# swd.net
KiCad netlist of a schematic drawn in EAGLE
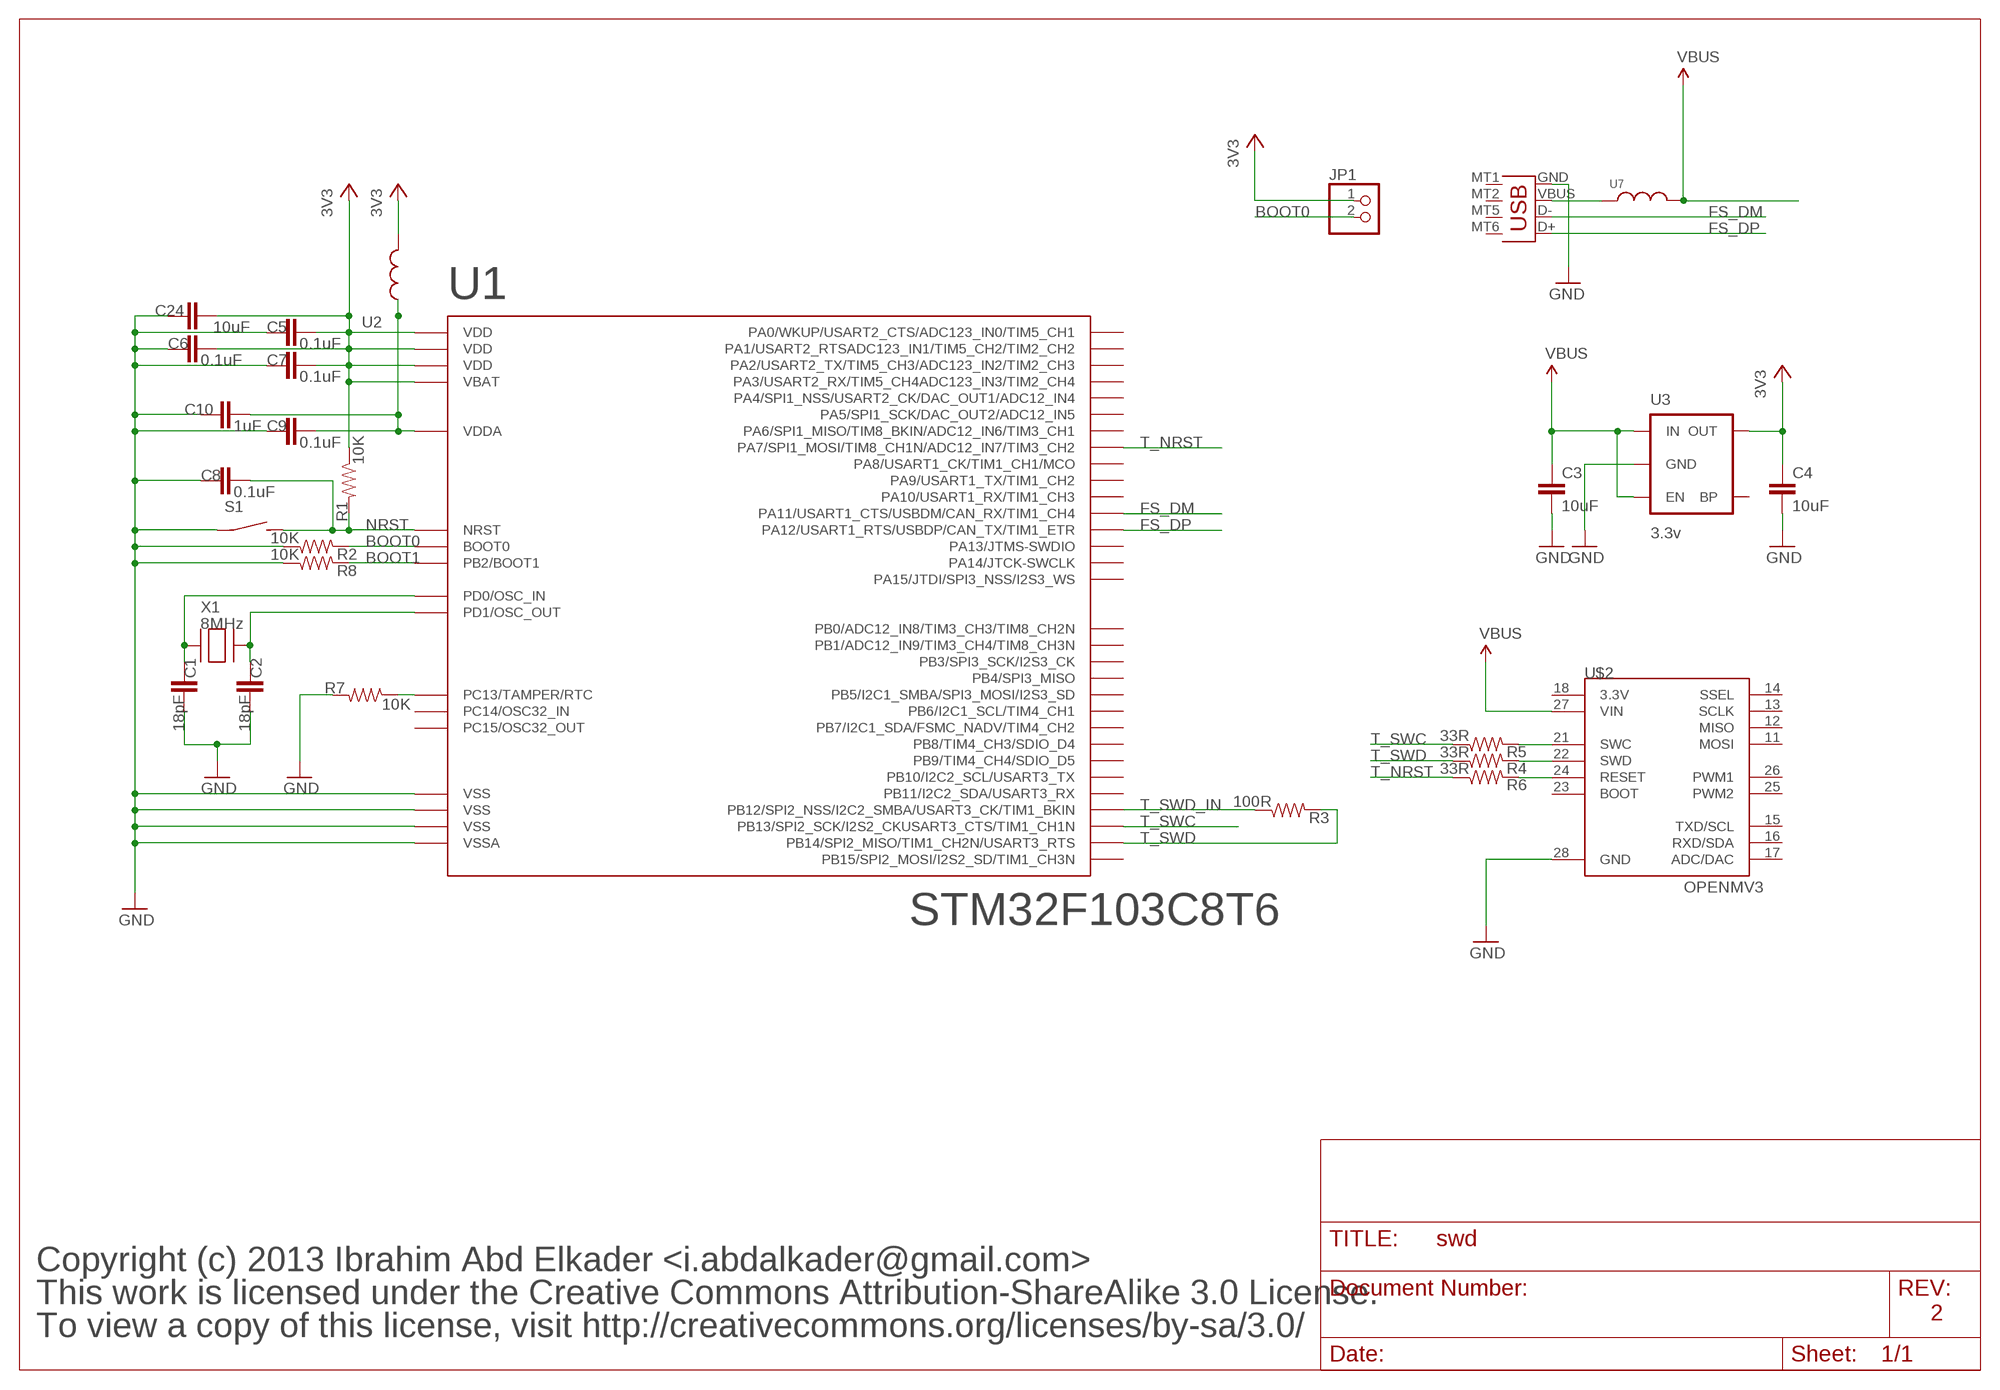
[diagram p0: schematic, sheet 1]

(export (version "E")
  (design (tool "Eeschema 10.0.6"))
  (components
    (comp (ref "C1")
      (value "18pF")
      (footprint "eagle-import:0603-CAP")
      (libsource (lib "eagle-import") (part "CAP0603-CAP"))
    )
    (comp (ref "C2")
      (value "18pF")
      (footprint "eagle-import:0603-CAP")
      (libsource (lib "eagle-import") (part "CAP0603-CAP"))
    )
    (comp (ref "C3")
      (value "10uF")
      (footprint "eagle-import:0805")
      (libsource (lib "eagle-import") (part "CAP0805"))
    )
    (comp (ref "C4")
      (value "10uF")
      (footprint "eagle-import:0805")
      (libsource (lib "eagle-import") (part "CAP0805"))
    )
    (comp (ref "C5")
      (value "0.1uF")
      (footprint "eagle-import:0603-CAP")
      (libsource (lib "eagle-import") (part "CAP0603-CAP"))
    )
    (comp (ref "C6")
      (value "0.1uF")
      (footprint "eagle-import:0603-CAP")
      (libsource (lib "eagle-import") (part "CAP0603-CAP"))
    )
    (comp (ref "C7")
      (value "0.1uF")
      (footprint "eagle-import:0603-CAP")
      (libsource (lib "eagle-import") (part "CAP0603-CAP"))
    )
    (comp (ref "C8")
      (value "0.1uF")
      (footprint "eagle-import:0603-CAP")
      (libsource (lib "eagle-import") (part "CAP0603-CAP"))
    )
    (comp (ref "C9")
      (value "0.1uF")
      (footprint "eagle-import:0603-CAP")
      (libsource (lib "eagle-import") (part "CAP0603-CAP"))
    )
    (comp (ref "C10")
      (value "1uF")
      (footprint "eagle-import:0603-CAP")
      (libsource (lib "eagle-import") (part "CAP0603-CAP"))
    )
    (comp (ref "C24")
      (value "10uF")
      (footprint "eagle-import:0805")
      (libsource (lib "eagle-import") (part "CAP0805"))
    )
    (comp (ref "JP1")
      (value "PINHD-1X2")
      (footprint "eagle-import:1X02")
      (libsource (lib "eagle-import") (part "PINHD-1X2"))
    )
    (comp (ref "R1")
      (value "10K")
      (footprint "eagle-import:0603-RES")
      (libsource (lib "eagle-import") (part "RESISTOR0603-RES"))
    )
    (comp (ref "R2")
      (value "10K")
      (footprint "eagle-import:0603-RES")
      (libsource (lib "eagle-import") (part "RESISTOR0603-RES"))
    )
    (comp (ref "R3")
      (value "100R")
      (footprint "eagle-import:0603-RES")
      (libsource (lib "eagle-import") (part "RESISTOR0603-RES"))
    )
    (comp (ref "R4")
      (value "33R")
      (footprint "eagle-import:0603-RES")
      (libsource (lib "eagle-import") (part "RESISTOR0603-RES"))
    )
    (comp (ref "R5")
      (value "33R")
      (footprint "eagle-import:0603-RES")
      (libsource (lib "eagle-import") (part "RESISTOR0603-RES"))
    )
    (comp (ref "R6")
      (value "33R")
      (footprint "eagle-import:0603-RES")
      (libsource (lib "eagle-import") (part "RESISTOR0603-RES"))
    )
    (comp (ref "R7")
      (value "10K")
      (footprint "eagle-import:0603-RES")
      (libsource (lib "eagle-import") (part "RESISTOR0603-RES"))
    )
    (comp (ref "R8")
      (value "10K")
      (footprint "eagle-import:0603-RES")
      (libsource (lib "eagle-import") (part "RESISTOR0603-RES"))
    )
    (comp (ref "S1")
      (value "SPST_3X4X2")
      (footprint "eagle-import:3X4X2TACT")
      (libsource (lib "eagle-import") (part "SPST_3X4X2"))
    )
    (comp (ref "U$2")
      (value "OPENMV3")
      (footprint "eagle-import:OPENMV3")
      (libsource (lib "eagle-import") (part "OPENMV3"))
    )
    (comp (ref "U1")
      (value "STM32F103C8T6")
      (footprint "eagle-import:LQFP48")
      (libsource (lib "eagle-import") (part "STM32F103C8T6"))
    )
    (comp (ref "U2")
      (value "INDUCTOR0603")
      (footprint "eagle-import:0603")
      (libsource (lib "eagle-import") (part "INDUCTOR0603"))
    )
    (comp (ref "U3")
      (value "3.3v")
      (footprint "eagle-import:SOT23-5")
      (libsource (lib "eagle-import") (part "V_REG_LDOSMD"))
    )
    (comp (ref "U7")
      (value "INDUCTOR0603")
      (footprint "eagle-import:0603")
      (libsource (lib "eagle-import") (part "INDUCTOR0603"))
    )
    (comp (ref "X1")
      (value "8MHz")
      (footprint "eagle-import:NX5032")
      (libsource (lib "eagle-import") (part "XTALNX5032"))
    )
    (comp (ref "X2")
      (value "USB-MICROB")
      (footprint "eagle-import:USB-MICROB")
      (libsource (lib "eagle-import") (part "USB-MICROB"))
    )
  )
  (nets
    (net (code "1") (name "/3.3V") (class "Default")
      (node (ref "U$2") (pin "18") (pinfunction "3.3V_18") (pintype "power_in"))
    )
    (net (code "2") (name "/BOOT0") (class "Default")
      (node (ref "JP1") (pin "2") (pinfunction "2_2") (pintype "passive"))
      (node (ref "R2") (pin "2") (pinfunction "2_2") (pintype "passive"))
      (node (ref "U1") (pin "44") (pinfunction "BOOT0_44") (pintype "bidirectional"))
    )
    (net (code "3") (name "/BOOT1") (class "Default")
      (node (ref "R8") (pin "2") (pinfunction "2_2") (pintype "passive"))
      (node (ref "U1") (pin "20") (pinfunction "PB2/BOOT1_20") (pintype "bidirectional"))
    )
    (net (code "4") (name "/FS_DM") (class "Default")
      (node (ref "U1") (pin "32") (pinfunction "PA11/USART1_CTS/USBDM/CAN_RX/TIM1_CH4_32") (pintype "bidirectional"))
      (node (ref "X2") (pin "D-") (pinfunction "D-_D-") (pintype "bidirectional"))
    )
    (net (code "5") (name "/FS_DP") (class "Default")
      (node (ref "U1") (pin "33") (pinfunction "PA12/USART1_RTS/USBDP/CAN_TX/TIM1_ETR_33") (pintype "bidirectional"))
      (node (ref "X2") (pin "D+") (pinfunction "D+_D+") (pintype "bidirectional"))
    )
    (net (code "6") (name "/NRST") (class "Default")
      (node (ref "C8") (pin "2") (pinfunction "2_2") (pintype "passive"))
      (node (ref "R1") (pin "2") (pinfunction "2_2") (pintype "passive"))
      (node (ref "S1") (pin "P$2") (pinfunction "S_P$2") (pintype "passive"))
      (node (ref "U1") (pin "7") (pinfunction "NRST_7") (pintype "bidirectional"))
    )
    (net (code "7") (name "/T_NRST") (class "Default")
      (node (ref "R6") (pin "1") (pinfunction "1_1") (pintype "passive"))
      (node (ref "U1") (pin "17") (pinfunction "PA7/SPI1_MOSI/TIM8_CH1N/ADC12_IN7/TIM3_CH2_17") (pintype "bidirectional"))
    )
    (net (code "8") (name "/T_SWC") (class "Default")
      (node (ref "R5") (pin "1") (pinfunction "1_1") (pintype "passive"))
      (node (ref "U1") (pin "26") (pinfunction "PB13/SPI2_SCK/I2S2_CKUSART3_CTS/TIM1_CH1N_26") (pintype "bidirectional"))
    )
    (net (code "9") (name "/T_SWD") (class "Default")
      (node (ref "R3") (pin "2") (pinfunction "2_2") (pintype "passive"))
      (node (ref "R4") (pin "1") (pinfunction "1_1") (pintype "passive"))
      (node (ref "U1") (pin "27") (pinfunction "PB14/SPI2_MISO/TIM1_CH2N/USART3_RTS_27") (pintype "bidirectional"))
    )
    (net (code "10") (name "/T_SWD_IN") (class "Default")
      (node (ref "R3") (pin "1") (pinfunction "1_1") (pintype "passive"))
      (node (ref "U1") (pin "25") (pinfunction "PB12/SPI2_NSS/I2C2_SMBA/USART3_CK/TIM1_BKIN_25") (pintype "bidirectional"))
    )
    (net (code "11") (name "3V3") (class "Default")
      (node (ref "C24") (pin "2") (pinfunction "2_2") (pintype "passive"))
      (node (ref "C4") (pin "1") (pinfunction "1_1") (pintype "passive"))
      (node (ref "C5") (pin "2") (pinfunction "2_2") (pintype "passive"))
      (node (ref "C6") (pin "2") (pinfunction "2_2") (pintype "passive"))
      (node (ref "C7") (pin "2") (pinfunction "2_2") (pintype "passive"))
      (node (ref "JP1") (pin "1") (pinfunction "1_1") (pintype "passive"))
      (node (ref "R1") (pin "1") (pinfunction "1_1") (pintype "passive"))
      (node (ref "U1") (pin "1") (pinfunction "VBAT_1") (pintype "power_in"))
      (node (ref "U1") (pin "24") (pinfunction "VDD_24") (pintype "power_in"))
      (node (ref "U1") (pin "36") (pinfunction "VDD_36") (pintype "power_in"))
      (node (ref "U1") (pin "48") (pinfunction "VDD_48") (pintype "power_in"))
      (node (ref "U2") (pin "2") (pinfunction "2_2") (pintype "passive"))
      (node (ref "U3") (pin "5") (pinfunction "OUT_5") (pintype "passive"))
    )
    (net (code "12") (name "GND") (class "Default")
      (node (ref "C1") (pin "1") (pinfunction "1_1") (pintype "passive"))
      (node (ref "C10") (pin "1") (pinfunction "1_1") (pintype "passive"))
      (node (ref "C2") (pin "1") (pinfunction "1_1") (pintype "passive"))
      (node (ref "C24") (pin "1") (pinfunction "1_1") (pintype "passive"))
      (node (ref "C3") (pin "2") (pinfunction "2_2") (pintype "passive"))
      (node (ref "C4") (pin "2") (pinfunction "2_2") (pintype "passive"))
      (node (ref "C5") (pin "1") (pinfunction "1_1") (pintype "passive"))
      (node (ref "C6") (pin "1") (pinfunction "1_1") (pintype "passive"))
      (node (ref "C7") (pin "1") (pinfunction "1_1") (pintype "passive"))
      (node (ref "C8") (pin "1") (pinfunction "1_1") (pintype "passive"))
      (node (ref "C9") (pin "1") (pinfunction "1_1") (pintype "passive"))
      (node (ref "R2") (pin "1") (pinfunction "1_1") (pintype "passive"))
      (node (ref "R7") (pin "2") (pinfunction "2_2") (pintype "passive"))
      (node (ref "R8") (pin "1") (pinfunction "1_1") (pintype "passive"))
      (node (ref "S1") (pin "P$1") (pinfunction "P_P$1") (pintype "passive"))
      (node (ref "U$2") (pin "28") (pinfunction "GND_28") (pintype "power_in"))
      (node (ref "U1") (pin "23") (pinfunction "VSS_23") (pintype "power_in"))
      (node (ref "U1") (pin "35") (pinfunction "VSS_35") (pintype "power_in"))
      (node (ref "U1") (pin "47") (pinfunction "VSS_47") (pintype "power_in"))
      (node (ref "U1") (pin "8") (pinfunction "VSSA_8") (pintype "power_in"))
      (node (ref "U3") (pin "2") (pinfunction "GND_2") (pintype "input"))
      (node (ref "X2") (pin "GND") (pinfunction "GND_GND") (pintype "bidirectional"))
    )
    (net (code "13") (name "Net-(U$2-RESET)") (class "Default")
      (node (ref "R6") (pin "2") (pinfunction "2_2") (pintype "passive"))
      (node (ref "U$2") (pin "24") (pinfunction "RESET_24") (pintype "bidirectional"))
    )
    (net (code "14") (name "Net-(U$2-SWC)") (class "Default")
      (node (ref "R5") (pin "2") (pinfunction "2_2") (pintype "passive"))
      (node (ref "U$2") (pin "21") (pinfunction "SWC_21") (pintype "bidirectional"))
    )
    (net (code "15") (name "Net-(U$2-SWD)") (class "Default")
      (node (ref "R4") (pin "2") (pinfunction "2_2") (pintype "passive"))
      (node (ref "U$2") (pin "22") (pinfunction "SWD_22") (pintype "bidirectional"))
    )
    (net (code "16") (name "Net-(U1-PC13{slash}TAMPER{slash}RTC)") (class "Default")
      (node (ref "R7") (pin "1") (pinfunction "1_1") (pintype "passive"))
      (node (ref "U1") (pin "2") (pinfunction "PC13/TAMPER/RTC_2") (pintype "bidirectional"))
    )
    (net (code "17") (name "Net-(U1-PD0{slash}OSC_IN)") (class "Default")
      (node (ref "C1") (pin "2") (pinfunction "2_2") (pintype "passive"))
      (node (ref "U1") (pin "5") (pinfunction "PD0/OSC_IN_5") (pintype "bidirectional"))
      (node (ref "X1") (pin "P$1") (pinfunction "P$1_P$1") (pintype "bidirectional"))
    )
    (net (code "18") (name "Net-(U1-PD1{slash}OSC_OUT)") (class "Default")
      (node (ref "C2") (pin "2") (pinfunction "2_2") (pintype "passive"))
      (node (ref "U1") (pin "6") (pinfunction "PD1/OSC_OUT_6") (pintype "bidirectional"))
      (node (ref "X1") (pin "P$2") (pinfunction "P$2_P$2") (pintype "bidirectional"))
    )
    (net (code "19") (name "Net-(U1-VDDA)") (class "Default")
      (node (ref "C10") (pin "2") (pinfunction "2_2") (pintype "passive"))
      (node (ref "C9") (pin "2") (pinfunction "2_2") (pintype "passive"))
      (node (ref "U1") (pin "9") (pinfunction "VDDA_9") (pintype "power_in"))
      (node (ref "U2") (pin "1") (pinfunction "1_1") (pintype "passive"))
    )
    (net (code "20") (name "Net-(U7-Pad1)") (class "Default")
      (node (ref "U7") (pin "1") (pinfunction "1_1") (pintype "passive"))
      (node (ref "X2") (pin "VBUS") (pinfunction "VBUS_VBUS") (pintype "bidirectional"))
    )
    (net (code "21") (name "VBUS") (class "Default")
      (node (ref "C3") (pin "1") (pinfunction "1_1") (pintype "passive"))
      (node (ref "U$2") (pin "27") (pinfunction "VIN_27") (pintype "power_in"))
      (node (ref "U3") (pin "1") (pinfunction "IN_1") (pintype "input"))
      (node (ref "U3") (pin "3") (pinfunction "EN_3") (pintype "input"))
      (node (ref "U7") (pin "2") (pinfunction "2_2") (pintype "passive"))
    )
    (net (code "22") (name "unconnected-(U$2-ADC{slash}DAC-Pad17)") (class "Default")
      (node (ref "U$2") (pin "17") (pinfunction "ADC/DAC_17") (pintype "bidirectional"))
    )
    (net (code "23") (name "unconnected-(U$2-BOOT-Pad23)") (class "Default")
      (node (ref "U$2") (pin "23") (pinfunction "BOOT_23") (pintype "bidirectional"))
    )
    (net (code "24") (name "unconnected-(U$2-MISO-Pad12)") (class "Default")
      (node (ref "U$2") (pin "12") (pinfunction "MISO_12") (pintype "bidirectional"))
    )
    (net (code "25") (name "unconnected-(U$2-MOSI-Pad11)") (class "Default")
      (node (ref "U$2") (pin "11") (pinfunction "MOSI_11") (pintype "bidirectional"))
    )
    (net (code "26") (name "unconnected-(U$2-PWM1-Pad26)") (class "Default")
      (node (ref "U$2") (pin "26") (pinfunction "PWM1_26") (pintype "bidirectional"))
    )
    (net (code "27") (name "unconnected-(U$2-PWM2-Pad25)") (class "Default")
      (node (ref "U$2") (pin "25") (pinfunction "PWM2_25") (pintype "bidirectional"))
    )
    (net (code "28") (name "unconnected-(U$2-RXD{slash}SDA-Pad16)") (class "Default")
      (node (ref "U$2") (pin "16") (pinfunction "RXD/SDA_16") (pintype "bidirectional"))
    )
    (net (code "29") (name "unconnected-(U$2-SCLK-Pad13)") (class "Default")
      (node (ref "U$2") (pin "13") (pinfunction "SCLK_13") (pintype "bidirectional"))
    )
    (net (code "30") (name "unconnected-(U$2-SSEL-Pad14)") (class "Default")
      (node (ref "U$2") (pin "14") (pinfunction "SSEL_14") (pintype "bidirectional"))
    )
    (net (code "31") (name "unconnected-(U$2-TXD{slash}SCL-Pad15)") (class "Default")
      (node (ref "U$2") (pin "15") (pinfunction "TXD/SCL_15") (pintype "bidirectional"))
    )
    (net (code "32") (name "unconnected-(U1-PA0{slash}WKUP{slash}USART2_CTS{slash}ADC123_IN0{slash}TIM5_CH1-Pad10)") (class "Default")
      (node (ref "U1") (pin "10") (pinfunction "PA0/WKUP/USART2_CTS/ADC123_IN0/TIM5_CH1_10") (pintype "bidirectional"))
    )
    (net (code "33") (name "unconnected-(U1-PA1{slash}USART2_RTSADC123_IN1{slash}TIM5_CH2{slash}TIM2_CH2-Pad11)") (class "Default")
      (node (ref "U1") (pin "11") (pinfunction "PA1/USART2_RTSADC123_IN1/TIM5_CH2/TIM2_CH2_11") (pintype "bidirectional"))
    )
    (net (code "34") (name "unconnected-(U1-PA2{slash}USART2_TX{slash}TIM5_CH3{slash}ADC123_IN2{slash}TIM2_CH3-Pad12)") (class "Default")
      (node (ref "U1") (pin "12") (pinfunction "PA2/USART2_TX/TIM5_CH3/ADC123_IN2/TIM2_CH3_12") (pintype "bidirectional"))
    )
    (net (code "35") (name "unconnected-(U1-PA3{slash}USART2_RX{slash}TIM5_CH4ADC123_IN3{slash}TIM2_CH4-Pad13)") (class "Default")
      (node (ref "U1") (pin "13") (pinfunction "PA3/USART2_RX/TIM5_CH4ADC123_IN3/TIM2_CH4_13") (pintype "bidirectional"))
    )
    (net (code "36") (name "unconnected-(U1-PA4{slash}SPI1_NSS{slash}USART2_CK{slash}DAC_OUT1{slash}ADC12_IN4-Pad14)") (class "Default")
      (node (ref "U1") (pin "14") (pinfunction "PA4/SPI1_NSS/USART2_CK/DAC_OUT1/ADC12_IN4_14") (pintype "bidirectional"))
    )
    (net (code "37") (name "unconnected-(U1-PA5{slash}SPI1_SCK{slash}DAC_OUT2{slash}ADC12_IN5-Pad15)") (class "Default")
      (node (ref "U1") (pin "15") (pinfunction "PA5/SPI1_SCK/DAC_OUT2/ADC12_IN5_15") (pintype "bidirectional"))
    )
    (net (code "38") (name "unconnected-(U1-PA6{slash}SPI1_MISO{slash}TIM8_BKIN{slash}ADC12_IN6{slash}TIM3_CH1-Pad16)") (class "Default")
      (node (ref "U1") (pin "16") (pinfunction "PA6/SPI1_MISO/TIM8_BKIN/ADC12_IN6/TIM3_CH1_16") (pintype "bidirectional"))
    )
    (net (code "39") (name "unconnected-(U1-PA8{slash}USART1_CK{slash}TIM1_CH1{slash}MCO-Pad29)") (class "Default")
      (node (ref "U1") (pin "29") (pinfunction "PA8/USART1_CK/TIM1_CH1/MCO_29") (pintype "bidirectional"))
    )
    (net (code "40") (name "unconnected-(U1-PA9{slash}USART1_TX{slash}TIM1_CH2-Pad30)") (class "Default")
      (node (ref "U1") (pin "30") (pinfunction "PA9/USART1_TX/TIM1_CH2_30") (pintype "bidirectional"))
    )
    (net (code "41") (name "unconnected-(U1-PA10{slash}USART1_RX{slash}TIM1_CH3-Pad31)") (class "Default")
      (node (ref "U1") (pin "31") (pinfunction "PA10/USART1_RX/TIM1_CH3_31") (pintype "bidirectional"))
    )
    (net (code "42") (name "unconnected-(U1-PA13{slash}JTMS-SWDIO-Pad34)") (class "Default")
      (node (ref "U1") (pin "34") (pinfunction "PA13/JTMS-SWDIO_34") (pintype "bidirectional"))
    )
    (net (code "43") (name "unconnected-(U1-PA14{slash}JTCK-SWCLK-Pad37)") (class "Default")
      (node (ref "U1") (pin "37") (pinfunction "PA14/JTCK-SWCLK_37") (pintype "bidirectional"))
    )
    (net (code "44") (name "unconnected-(U1-PA15{slash}JTDI{slash}SPI3_NSS{slash}I2S3_WS-Pad38)") (class "Default")
      (node (ref "U1") (pin "38") (pinfunction "PA15/JTDI/SPI3_NSS/I2S3_WS_38") (pintype "bidirectional"))
    )
    (net (code "45") (name "unconnected-(U1-PB0{slash}ADC12_IN8{slash}TIM3_CH3{slash}TIM8_CH2N-Pad18)") (class "Default")
      (node (ref "U1") (pin "18") (pinfunction "PB0/ADC12_IN8/TIM3_CH3/TIM8_CH2N_18") (pintype "bidirectional"))
    )
    (net (code "46") (name "unconnected-(U1-PB1{slash}ADC12_IN9{slash}TIM3_CH4{slash}TIM8_CH3N-Pad19)") (class "Default")
      (node (ref "U1") (pin "19") (pinfunction "PB1/ADC12_IN9/TIM3_CH4/TIM8_CH3N_19") (pintype "bidirectional"))
    )
    (net (code "47") (name "unconnected-(U1-PB3{slash}SPI3_SCK{slash}I2S3_CK-Pad39)") (class "Default")
      (node (ref "U1") (pin "39") (pinfunction "PB3/SPI3_SCK/I2S3_CK_39") (pintype "bidirectional"))
    )
    (net (code "48") (name "unconnected-(U1-PB4{slash}SPI3_MISO-Pad40)") (class "Default")
      (node (ref "U1") (pin "40") (pinfunction "PB4/SPI3_MISO_40") (pintype "bidirectional"))
    )
    (net (code "49") (name "unconnected-(U1-PB5{slash}I2C1_SMBA{slash}SPI3_MOSI{slash}I2S3_SD-Pad41)") (class "Default")
      (node (ref "U1") (pin "41") (pinfunction "PB5/I2C1_SMBA/SPI3_MOSI/I2S3_SD_41") (pintype "bidirectional"))
    )
    (net (code "50") (name "unconnected-(U1-PB6{slash}I2C1_SCL{slash}TIM4_CH1-Pad42)") (class "Default")
      (node (ref "U1") (pin "42") (pinfunction "PB6/I2C1_SCL/TIM4_CH1_42") (pintype "bidirectional"))
    )
    (net (code "51") (name "unconnected-(U1-PB7{slash}I2C1_SDA{slash}FSMC_NADV{slash}TIM4_CH2-Pad43)") (class "Default")
      (node (ref "U1") (pin "43") (pinfunction "PB7/I2C1_SDA/FSMC_NADV/TIM4_CH2_43") (pintype "bidirectional"))
    )
    (net (code "52") (name "unconnected-(U1-PB8{slash}TIM4_CH3{slash}SDIO_D4-Pad45)") (class "Default")
      (node (ref "U1") (pin "45") (pinfunction "PB8/TIM4_CH3/SDIO_D4_45") (pintype "bidirectional"))
    )
    (net (code "53") (name "unconnected-(U1-PB9{slash}TIM4_CH4{slash}SDIO_D5-Pad46)") (class "Default")
      (node (ref "U1") (pin "46") (pinfunction "PB9/TIM4_CH4/SDIO_D5_46") (pintype "bidirectional"))
    )
    (net (code "54") (name "unconnected-(U1-PB10{slash}I2C2_SCL{slash}USART3_TX-Pad21)") (class "Default")
      (node (ref "U1") (pin "21") (pinfunction "PB10/I2C2_SCL/USART3_TX_21") (pintype "bidirectional"))
    )
    (net (code "55") (name "unconnected-(U1-PB11{slash}I2C2_SDA{slash}USART3_RX-Pad22)") (class "Default")
      (node (ref "U1") (pin "22") (pinfunction "PB11/I2C2_SDA/USART3_RX_22") (pintype "bidirectional"))
    )
    (net (code "56") (name "unconnected-(U1-PB15{slash}SPI2_MOSI{slash}I2S2_SD{slash}TIM1_CH3N-Pad28)") (class "Default")
      (node (ref "U1") (pin "28") (pinfunction "PB15/SPI2_MOSI/I2S2_SD/TIM1_CH3N_28") (pintype "bidirectional"))
    )
    (net (code "57") (name "unconnected-(U1-PC14{slash}OSC32_IN-Pad3)") (class "Default")
      (node (ref "U1") (pin "3") (pinfunction "PC14/OSC32_IN_3") (pintype "bidirectional"))
    )
    (net (code "58") (name "unconnected-(U1-PC15{slash}OSC32_OUT-Pad4)") (class "Default")
      (node (ref "U1") (pin "4") (pinfunction "PC15/OSC32_OUT_4") (pintype "bidirectional"))
    )
    (net (code "59") (name "unconnected-(U3-BP-Pad4)") (class "Default")
      (node (ref "U3") (pin "4") (pinfunction "BP_4") (pintype "input"))
    )
    (net (code "60") (name "unconnected-(X2-GND1-PadMT1)") (class "Default")
      (node (ref "X2") (pin "MT1") (pinfunction "GND1_MT1") (pintype "passive"))
    )
    (net (code "61") (name "unconnected-(X2-GND2-PadMT2)") (class "Default")
      (node (ref "X2") (pin "MT2") (pinfunction "GND2_MT2") (pintype "passive"))
    )
    (net (code "62") (name "unconnected-(X2-GND3-PadMT5)") (class "Default")
      (node (ref "X2") (pin "MT5") (pinfunction "GND3_MT5") (pintype "passive"))
    )
    (net (code "63") (name "unconnected-(X2-GND4-PadMT6)") (class "Default")
      (node (ref "X2") (pin "MT6") (pinfunction "GND4_MT6") (pintype "passive"))
    )
  )
)
